# ButtonPCB.net
KiCad netlist of a schematic drawn in EAGLE
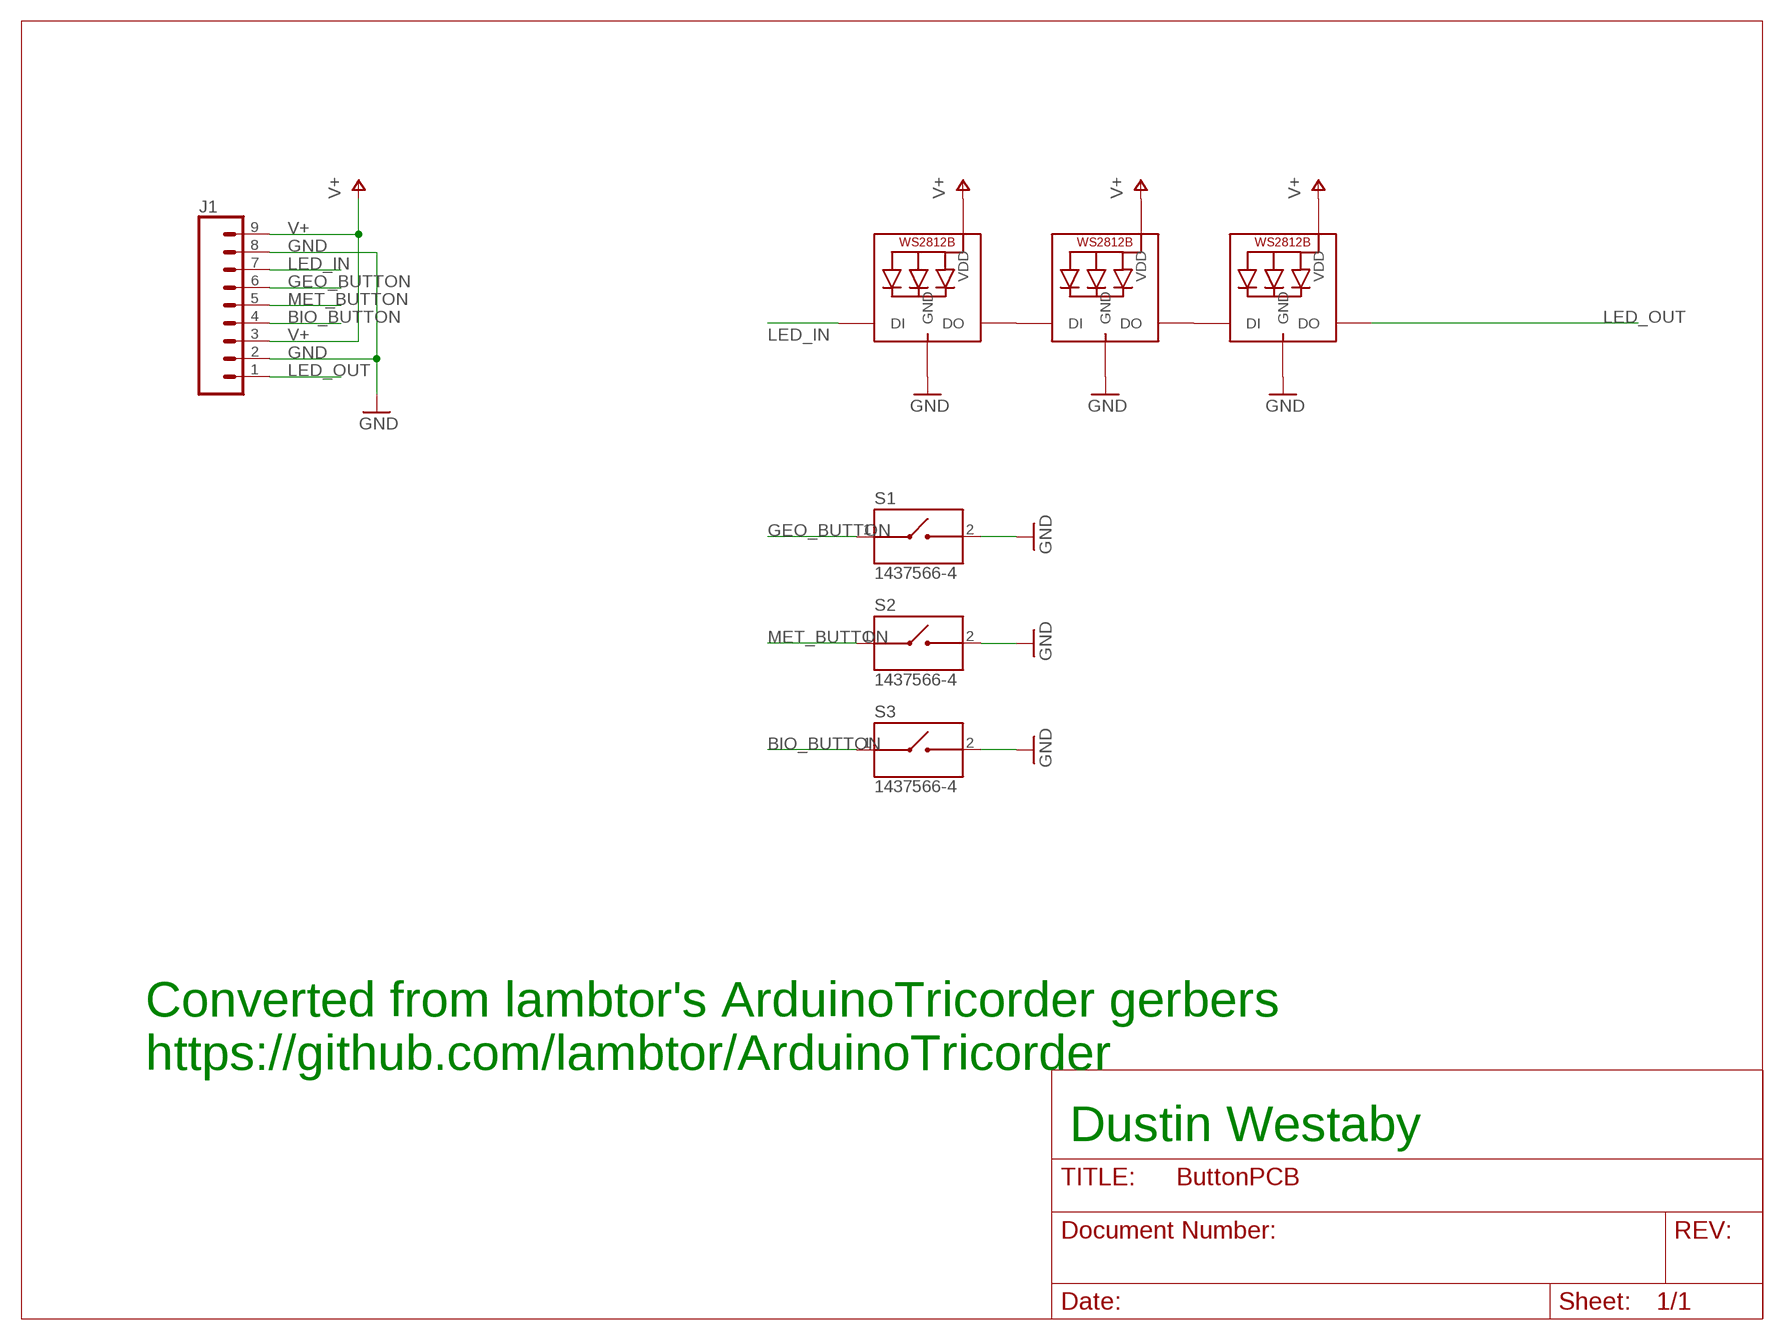
[diagram p0: schematic, sheet 1]

(export (version "E")
  (design (tool "Eeschema 10.0.6"))
  (components
    (comp (ref "J1")
      (value "CONN_09")
      (footprint "eagle-import:1X09")
      (libsource (lib "eagle-import") (part "CONN_09"))
    )
    (comp (ref "LED1")
      (value "WS2812B_4020")
      (footprint "eagle-import:WS2812B_4020")
      (libsource (lib "eagle-import") (part "WS2812B_4020"))
    )
    (comp (ref "LED2")
      (value "WS2812B_4020")
      (footprint "eagle-import:WS2812B_4020")
      (libsource (lib "eagle-import") (part "WS2812B_4020"))
    )
    (comp (ref "LED3")
      (value "WS2812B_4020")
      (footprint "eagle-import:WS2812B_4020")
      (libsource (lib "eagle-import") (part "WS2812B_4020"))
    )
    (comp (ref "S1")
      (value "1437566-4")
      (footprint "eagle-import:SW_1437566-4")
      (fields
        (field (name "DIGI-KEY_PART_NUMBER") "2266-1437569-2TR-ND")
        (field (name "MF") "TE Connectivity")
      )
      (libsource (lib "eagle-import") (part "1437566-4"))
    )
    (comp (ref "S2")
      (value "1437566-4")
      (footprint "eagle-import:SW_1437566-4")
      (fields
        (field (name "DIGI-KEY_PART_NUMBER") "2266-1437569-2TR-ND")
        (field (name "MF") "TE Connectivity")
      )
      (libsource (lib "eagle-import") (part "1437566-4"))
    )
    (comp (ref "S3")
      (value "1437566-4")
      (footprint "eagle-import:SW_1437566-4")
      (fields
        (field (name "DIGI-KEY_PART_NUMBER") "2266-1437569-2TR-ND")
        (field (name "MF") "TE Connectivity")
      )
      (libsource (lib "eagle-import") (part "1437566-4"))
    )
  )
  (nets
    (net (code "1") (name "/BIO_BUTTON") (class "Default")
      (node (ref "J1") (pin "4") (pinfunction "4_4") (pintype "passive"))
      (node (ref "S3") (pin "1") (pinfunction "1_1") (pintype "passive"))
    )
    (net (code "2") (name "/GEO_BUTTON") (class "Default")
      (node (ref "J1") (pin "6") (pinfunction "6_6") (pintype "passive"))
      (node (ref "S1") (pin "1") (pinfunction "1_1") (pintype "passive"))
    )
    (net (code "3") (name "/LED_IN") (class "Default")
      (node (ref "J1") (pin "7") (pinfunction "7_7") (pintype "passive"))
      (node (ref "LED2") (pin "1") (pinfunction "DI_1") (pintype "input"))
    )
    (net (code "4") (name "/LED_OUT") (class "Default")
      (node (ref "J1") (pin "1") (pinfunction "1_1") (pintype "passive"))
      (node (ref "LED3") (pin "3") (pinfunction "DO_3") (pintype "output"))
    )
    (net (code "5") (name "/MET_BUTTON") (class "Default")
      (node (ref "J1") (pin "5") (pinfunction "5_5") (pintype "passive"))
      (node (ref "S2") (pin "1") (pinfunction "1_1") (pintype "passive"))
    )
    (net (code "6") (name "GND") (class "Default")
      (node (ref "J1") (pin "2") (pinfunction "2_2") (pintype "passive"))
      (node (ref "J1") (pin "8") (pinfunction "8_8") (pintype "passive"))
      (node (ref "LED1") (pin "4") (pinfunction "GND_4") (pintype "power_in"))
      (node (ref "LED2") (pin "4") (pinfunction "GND_4") (pintype "power_in"))
      (node (ref "LED3") (pin "4") (pinfunction "GND_4") (pintype "power_in"))
      (node (ref "S1") (pin "2") (pinfunction "2_2") (pintype "passive"))
      (node (ref "S2") (pin "2") (pinfunction "2_2") (pintype "passive"))
      (node (ref "S3") (pin "2") (pinfunction "2_2") (pintype "passive"))
    )
    (net (code "7") (name "Net-(LED1-DI)") (class "Default")
      (node (ref "LED1") (pin "1") (pinfunction "DI_1") (pintype "input"))
      (node (ref "LED2") (pin "3") (pinfunction "DO_3") (pintype "output"))
    )
    (net (code "8") (name "Net-(LED1-DO)") (class "Default")
      (node (ref "LED1") (pin "3") (pinfunction "DO_3") (pintype "output"))
      (node (ref "LED3") (pin "1") (pinfunction "DI_1") (pintype "input"))
    )
    (net (code "9") (name "V+") (class "Default")
      (node (ref "J1") (pin "3") (pinfunction "3_3") (pintype "passive"))
      (node (ref "J1") (pin "9") (pinfunction "9_9") (pintype "passive"))
      (node (ref "LED1") (pin "2") (pinfunction "VDD_2") (pintype "power_in"))
      (node (ref "LED2") (pin "2") (pinfunction "VDD_2") (pintype "power_in"))
      (node (ref "LED3") (pin "2") (pinfunction "VDD_2") (pintype "power_in"))
    )
  )
)
